# 7SEGMENT.net
KiCad netlist of a schematic drawn in Altium Designer
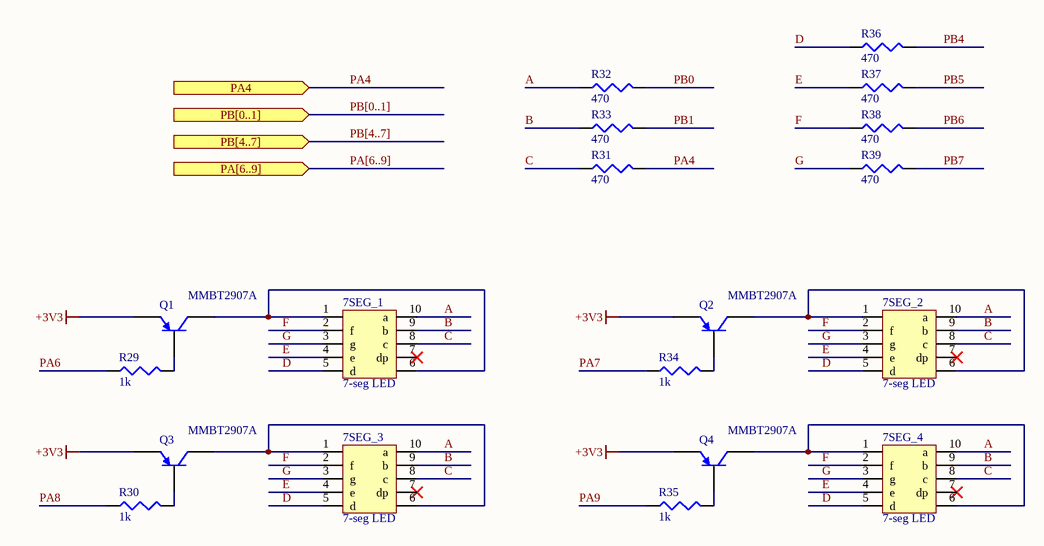
[diagram p0: 7SEGMENT.SchDoc]

(export (version "E")
  (design (tool "Eeschema 10.0.6"))
  (components
    (comp (ref "7SEG_1")
      (value "7-seg LED")
      (footprint "7-seg LED 0.36inch")
      (libsource (lib "Ho Chi Minh City University of Technology") (part "7-seg LED"))
    )
    (comp (ref "7SEG_2")
      (value "7-seg LED")
      (footprint "7-seg LED 0.36inch")
      (libsource (lib "Ho Chi Minh City University of Technology") (part "7-seg LED"))
    )
    (comp (ref "7SEG_3")
      (value "7-seg LED")
      (footprint "7-seg LED 0.36inch")
      (libsource (lib "Ho Chi Minh City University of Technology") (part "7-seg LED"))
    )
    (comp (ref "7SEG_4")
      (value "7-seg LED")
      (footprint "7-seg LED 0.36inch")
      (libsource (lib "Ho Chi Minh City University of Technology") (part "7-seg LED"))
    )
    (comp (ref "Q1")
      (value "MMBT2907A")
      (footprint "FAIR-SOT23-3_V")
      (fields
        (field (name "POWER") "350mW")
        (field (name "JLCPCB PART #") "C2972764")
        (field (name "MANUFACTURER") "Fairchild")
      )
      (libsource (lib "Ho Chi Minh City University of Technology") (part "BJT-PNP-BEC-3"))
    )
    (comp (ref "Q2")
      (value "MMBT2907A")
      (footprint "FAIR-SOT23-3_V")
      (fields
        (field (name "POWER") "350mW")
        (field (name "JLCPCB PART #") "C2972764")
        (field (name "MANUFACTURER") "Fairchild")
      )
      (libsource (lib "Ho Chi Minh City University of Technology") (part "BJT-PNP-BEC-3"))
    )
    (comp (ref "Q3")
      (value "MMBT2907A")
      (footprint "FAIR-SOT23-3_V")
      (fields
        (field (name "POWER") "350mW")
        (field (name "JLCPCB PART #") "C2972764")
        (field (name "MANUFACTURER") "Fairchild")
      )
      (libsource (lib "Ho Chi Minh City University of Technology") (part "BJT-PNP-BEC-3"))
    )
    (comp (ref "Q4")
      (value "MMBT2907A")
      (footprint "FAIR-SOT23-3_V")
      (fields
        (field (name "POWER") "350mW")
        (field (name "JLCPCB PART #") "C2972764")
        (field (name "MANUFACTURER") "Fairchild")
      )
      (libsource (lib "Ho Chi Minh City University of Technology") (part "BJT-PNP-BEC-3"))
    )
    (comp (ref "R29")
      (value "1k")
      (footprint "0805 (2012 Metric)")
      (description "Oreki")
      (libsource (lib "Ho Chi Minh City University of Technology") (part "RES-2"))
    )
    (comp (ref "R30")
      (value "1k")
      (footprint "0805 (2012 Metric)")
      (description "Oreki")
      (libsource (lib "Ho Chi Minh City University of Technology") (part "RES-2"))
    )
    (comp (ref "R31")
      (value "470")
      (footprint "0805 (2012 Metric)")
      (description "Oreki")
      (libsource (lib "Ho Chi Minh City University of Technology") (part "RES-2"))
    )
    (comp (ref "R32")
      (value "470")
      (footprint "0805 (2012 Metric)")
      (description "Oreki")
      (libsource (lib "Ho Chi Minh City University of Technology") (part "RES-2"))
    )
    (comp (ref "R33")
      (value "470")
      (footprint "0805 (2012 Metric)")
      (description "Oreki")
      (libsource (lib "Ho Chi Minh City University of Technology") (part "RES-2"))
    )
    (comp (ref "R34")
      (value "1k")
      (footprint "0805 (2012 Metric)")
      (description "Oreki")
      (libsource (lib "Ho Chi Minh City University of Technology") (part "RES-2"))
    )
    (comp (ref "R35")
      (value "1k")
      (footprint "0805 (2012 Metric)")
      (description "Oreki")
      (libsource (lib "Ho Chi Minh City University of Technology") (part "RES-2"))
    )
    (comp (ref "R36")
      (value "470")
      (footprint "0805 (2012 Metric)")
      (description "Oreki")
      (libsource (lib "Ho Chi Minh City University of Technology") (part "RES-2"))
    )
    (comp (ref "R37")
      (value "470")
      (footprint "0805 (2012 Metric)")
      (description "Oreki")
      (libsource (lib "Ho Chi Minh City University of Technology") (part "RES-2"))
    )
    (comp (ref "R38")
      (value "470")
      (footprint "0805 (2012 Metric)")
      (description "Oreki")
      (libsource (lib "Ho Chi Minh City University of Technology") (part "RES-2"))
    )
    (comp (ref "R39")
      (value "470")
      (footprint "0805 (2012 Metric)")
      (description "Oreki")
      (libsource (lib "Ho Chi Minh City University of Technology") (part "RES-2"))
    )
  )
  (nets
    (net (code "1") (name "+3V3") (class "Default")
      (node (ref "Q1") (pin "2") (pinfunction "E_2") (pintype "passive"))
      (node (ref "Q2") (pin "2") (pinfunction "E_2") (pintype "passive"))
      (node (ref "Q3") (pin "2") (pinfunction "E_2") (pintype "passive"))
      (node (ref "Q4") (pin "2") (pinfunction "E_2") (pintype "passive"))
    )
    (net (code "2") (name "/A") (class "Default")
      (node (ref "7SEG_1") (pin "10") (pinfunction "a_10") (pintype "passive"))
      (node (ref "7SEG_2") (pin "10") (pinfunction "a_10") (pintype "passive"))
      (node (ref "7SEG_3") (pin "10") (pinfunction "a_10") (pintype "passive"))
      (node (ref "7SEG_4") (pin "10") (pinfunction "a_10") (pintype "passive"))
      (node (ref "R32") (pin "1") (pinfunction "1_1") (pintype "passive"))
    )
    (net (code "3") (name "/B") (class "Default")
      (node (ref "7SEG_1") (pin "9") (pinfunction "b_9") (pintype "passive"))
      (node (ref "7SEG_2") (pin "9") (pinfunction "b_9") (pintype "passive"))
      (node (ref "7SEG_3") (pin "9") (pinfunction "b_9") (pintype "passive"))
      (node (ref "7SEG_4") (pin "9") (pinfunction "b_9") (pintype "passive"))
      (node (ref "R33") (pin "1") (pinfunction "1_1") (pintype "passive"))
    )
    (net (code "4") (name "/C") (class "Default")
      (node (ref "7SEG_1") (pin "8") (pinfunction "c_8") (pintype "passive"))
      (node (ref "7SEG_2") (pin "8") (pinfunction "c_8") (pintype "passive"))
      (node (ref "7SEG_3") (pin "8") (pinfunction "c_8") (pintype "passive"))
      (node (ref "7SEG_4") (pin "8") (pinfunction "c_8") (pintype "passive"))
      (node (ref "R31") (pin "1") (pinfunction "1_1") (pintype "passive"))
    )
    (net (code "5") (name "/D") (class "Default")
      (node (ref "7SEG_1") (pin "5") (pinfunction "d_5") (pintype "passive"))
      (node (ref "7SEG_2") (pin "5") (pinfunction "d_5") (pintype "passive"))
      (node (ref "7SEG_3") (pin "5") (pinfunction "d_5") (pintype "passive"))
      (node (ref "7SEG_4") (pin "5") (pinfunction "d_5") (pintype "passive"))
      (node (ref "R36") (pin "1") (pinfunction "1_1") (pintype "passive"))
    )
    (net (code "6") (name "/E") (class "Default")
      (node (ref "7SEG_1") (pin "4") (pinfunction "e_4") (pintype "passive"))
      (node (ref "7SEG_2") (pin "4") (pinfunction "e_4") (pintype "passive"))
      (node (ref "7SEG_3") (pin "4") (pinfunction "e_4") (pintype "passive"))
      (node (ref "7SEG_4") (pin "4") (pinfunction "e_4") (pintype "passive"))
      (node (ref "R37") (pin "1") (pinfunction "1_1") (pintype "passive"))
    )
    (net (code "7") (name "/F") (class "Default")
      (node (ref "7SEG_1") (pin "2") (pinfunction "f_2") (pintype "passive"))
      (node (ref "7SEG_2") (pin "2") (pinfunction "f_2") (pintype "passive"))
      (node (ref "7SEG_3") (pin "2") (pinfunction "f_2") (pintype "passive"))
      (node (ref "7SEG_4") (pin "2") (pinfunction "f_2") (pintype "passive"))
      (node (ref "R38") (pin "1") (pinfunction "1_1") (pintype "passive"))
    )
    (net (code "8") (name "/G") (class "Default")
      (node (ref "7SEG_1") (pin "3") (pinfunction "g_3") (pintype "passive"))
      (node (ref "7SEG_2") (pin "3") (pinfunction "g_3") (pintype "passive"))
      (node (ref "7SEG_3") (pin "3") (pinfunction "g_3") (pintype "passive"))
      (node (ref "7SEG_4") (pin "3") (pinfunction "g_3") (pintype "passive"))
      (node (ref "R39") (pin "1") (pinfunction "1_1") (pintype "passive"))
    )
    (net (code "9") (name "/PA4") (class "Default")
      (node (ref "R31") (pin "2") (pinfunction "2_2") (pintype "passive"))
    )
    (net (code "10") (name "/PA6") (class "Default")
      (node (ref "R29") (pin "1") (pinfunction "1_1") (pintype "passive"))
    )
    (net (code "11") (name "/PA7") (class "Default")
      (node (ref "R34") (pin "1") (pinfunction "1_1") (pintype "passive"))
    )
    (net (code "12") (name "/PA8") (class "Default")
      (node (ref "R30") (pin "1") (pinfunction "1_1") (pintype "passive"))
    )
    (net (code "13") (name "/PA9") (class "Default")
      (node (ref "R35") (pin "1") (pinfunction "1_1") (pintype "passive"))
    )
    (net (code "15") (name "/PB0") (class "Default")
      (node (ref "R32") (pin "2") (pinfunction "2_2") (pintype "passive"))
    )
    (net (code "16") (name "/PB1") (class "Default")
      (node (ref "R33") (pin "2") (pinfunction "2_2") (pintype "passive"))
    )
    (net (code "17") (name "/PB4") (class "Default")
      (node (ref "R36") (pin "2") (pinfunction "2_2") (pintype "passive"))
    )
    (net (code "18") (name "/PB5") (class "Default")
      (node (ref "R37") (pin "2") (pinfunction "2_2") (pintype "passive"))
    )
    (net (code "19") (name "/PB6") (class "Default")
      (node (ref "R38") (pin "2") (pinfunction "2_2") (pintype "passive"))
    )
    (net (code "20") (name "/PB7") (class "Default")
      (node (ref "R39") (pin "2") (pinfunction "2_2") (pintype "passive"))
    )
    (net (code "23") (name "Net-(7SEG_1-VCC{slash}GND)") (class "Default")
      (node (ref "7SEG_1") (pin "1") (pintype "passive"))
      (node (ref "7SEG_1") (pin "6") (pinfunction "VCC/GND_6") (pintype "passive"))
      (node (ref "Q1") (pin "3") (pinfunction "C_3") (pintype "passive"))
    )
    (net (code "24") (name "Net-(7SEG_2-VCC{slash}GND)") (class "Default")
      (node (ref "7SEG_2") (pin "1") (pintype "passive"))
      (node (ref "7SEG_2") (pin "6") (pinfunction "VCC/GND_6") (pintype "passive"))
      (node (ref "Q2") (pin "3") (pinfunction "C_3") (pintype "passive"))
    )
    (net (code "25") (name "Net-(7SEG_3-VCC{slash}GND)") (class "Default")
      (node (ref "7SEG_3") (pin "1") (pintype "passive"))
      (node (ref "7SEG_3") (pin "6") (pinfunction "VCC/GND_6") (pintype "passive"))
      (node (ref "Q3") (pin "3") (pinfunction "C_3") (pintype "passive"))
    )
    (net (code "26") (name "Net-(7SEG_4-VCC{slash}GND)") (class "Default")
      (node (ref "7SEG_4") (pin "1") (pintype "passive"))
      (node (ref "7SEG_4") (pin "6") (pinfunction "VCC/GND_6") (pintype "passive"))
      (node (ref "Q4") (pin "3") (pinfunction "C_3") (pintype "passive"))
    )
    (net (code "27") (name "Net-(Q1-B)") (class "Default")
      (node (ref "Q1") (pin "1") (pinfunction "B_1") (pintype "passive"))
      (node (ref "R29") (pin "2") (pinfunction "2_2") (pintype "passive"))
    )
    (net (code "28") (name "Net-(Q2-B)") (class "Default")
      (node (ref "Q2") (pin "1") (pinfunction "B_1") (pintype "passive"))
      (node (ref "R34") (pin "2") (pinfunction "2_2") (pintype "passive"))
    )
    (net (code "29") (name "Net-(Q3-B)") (class "Default")
      (node (ref "Q3") (pin "1") (pinfunction "B_1") (pintype "passive"))
      (node (ref "R30") (pin "2") (pinfunction "2_2") (pintype "passive"))
    )
    (net (code "30") (name "Net-(Q4-B)") (class "Default")
      (node (ref "Q4") (pin "1") (pinfunction "B_1") (pintype "passive"))
      (node (ref "R35") (pin "2") (pinfunction "2_2") (pintype "passive"))
    )
    (net (code "31") (name "unconnected-(7SEG_1-dp-Pad7)") (class "Default")
      (node (ref "7SEG_1") (pin "7") (pinfunction "dp_7") (pintype "passive+no_connect"))
    )
    (net (code "32") (name "unconnected-(7SEG_2-dp-Pad7)") (class "Default")
      (node (ref "7SEG_2") (pin "7") (pinfunction "dp_7") (pintype "passive+no_connect"))
    )
    (net (code "33") (name "unconnected-(7SEG_3-dp-Pad7)") (class "Default")
      (node (ref "7SEG_3") (pin "7") (pinfunction "dp_7") (pintype "passive+no_connect"))
    )
    (net (code "34") (name "unconnected-(7SEG_4-dp-Pad7)") (class "Default")
      (node (ref "7SEG_4") (pin "7") (pinfunction "dp_7") (pintype "passive+no_connect"))
    )
  )
)
